# Fonte_Sim_trica_12V.net
KiCad netlist of a schematic drawn in EAGLE
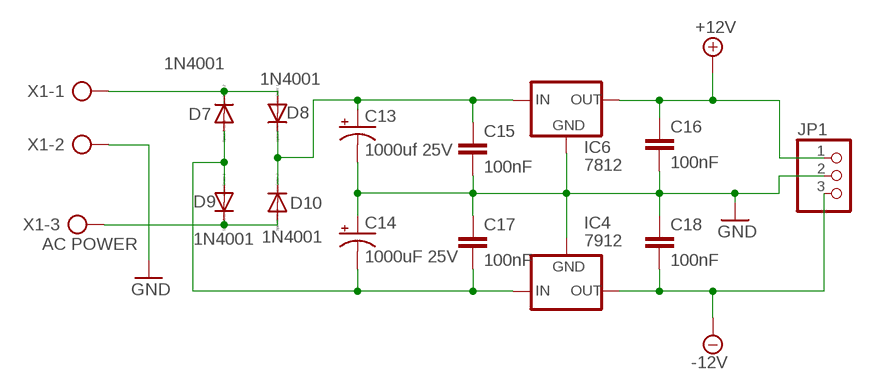
[diagram p0: schematic, sheet 1]

(export (version "E")
  (design (tool "Eeschema 10.0.6"))
  (components
    (comp (ref "C13")
      (value "1000uf 25V")
      (footprint "eagle-import:E5-10,5")
      (libsource (lib "eagle-import") (part "CPOL-USE5-10.5"))
    )
    (comp (ref "C14")
      (value "1000uF 25V")
      (footprint "eagle-import:E5-10,5")
      (libsource (lib "eagle-import") (part "CPOL-USE5-10.5"))
    )
    (comp (ref "C15")
      (value "100nF")
      (footprint "eagle-import:C025-040X050")
      (libsource (lib "eagle-import") (part "C-EU025-040X050"))
    )
    (comp (ref "C16")
      (value "100nF")
      (footprint "eagle-import:C025-040X050")
      (libsource (lib "eagle-import") (part "C-EU025-040X050"))
    )
    (comp (ref "C17")
      (value "100nF")
      (footprint "eagle-import:C025-040X050")
      (libsource (lib "eagle-import") (part "C-EU025-040X050"))
    )
    (comp (ref "C18")
      (value "100nF")
      (footprint "eagle-import:C025-040X050")
      (libsource (lib "eagle-import") (part "C-EU025-040X050"))
    )
    (comp (ref "D7")
      (value "1N4001")
      (footprint "eagle-import:DO41-10")
      (libsource (lib "eagle-import") (part "1N4004"))
    )
    (comp (ref "D8")
      (value "1N4001")
      (footprint "eagle-import:DO41-10")
      (libsource (lib "eagle-import") (part "1N4004"))
    )
    (comp (ref "D9")
      (value "1N4001")
      (footprint "eagle-import:DO41-10")
      (libsource (lib "eagle-import") (part "1N4004"))
    )
    (comp (ref "D10")
      (value "1N4001")
      (footprint "eagle-import:DO41-10")
      (libsource (lib "eagle-import") (part "1N4004"))
    )
    (comp (ref "IC4")
      (value "7912")
      (footprint "eagle-import:79XXS")
      (libsource (lib "eagle-import") (part "79XXS"))
    )
    (comp (ref "IC6")
      (value "7812")
      (footprint "eagle-import:78XXS")
      (libsource (lib "eagle-import") (part "78XXS"))
    )
    (comp (ref "JP1")
      (value "PINHD-1X3")
      (footprint "eagle-import:1X03")
      (libsource (lib "eagle-import") (part "PINHD-1X3"))
    )
    (comp (ref "X1")
      (value "AC POWER")
      (footprint "eagle-import:AK500_3")
      (libsource (lib "eagle-import") (part "AK500/3"))
    )
  )
  (nets
    (net (code "1") (name "+12V") (class "Default")
      (node (ref "C16") (pin "1") (pinfunction "1_1") (pintype "passive"))
      (node (ref "IC6") (pin "OUT") (pinfunction "OUT_OUT") (pintype "passive"))
      (node (ref "JP1") (pin "1") (pinfunction "1_1") (pintype "passive"))
    )
    (net (code "2") (name "-12V") (class "Default")
      (node (ref "C18") (pin "2") (pinfunction "2_2") (pintype "passive"))
      (node (ref "IC4") (pin "OUT") (pinfunction "OUT_OUT") (pintype "passive"))
      (node (ref "JP1") (pin "3") (pinfunction "3_3") (pintype "passive"))
    )
    (net (code "3") (name "GND") (class "Default")
      (node (ref "C13") (pin "-") (pinfunction "-_-") (pintype "passive"))
      (node (ref "C14") (pin "+") (pinfunction "+_+") (pintype "passive"))
      (node (ref "C15") (pin "2") (pinfunction "2_2") (pintype "passive"))
      (node (ref "C16") (pin "2") (pinfunction "2_2") (pintype "passive"))
      (node (ref "C17") (pin "1") (pinfunction "1_1") (pintype "passive"))
      (node (ref "C18") (pin "1") (pinfunction "1_1") (pintype "passive"))
      (node (ref "IC4") (pin "GND") (pinfunction "GND_GND") (pintype "input"))
      (node (ref "IC6") (pin "GND") (pinfunction "GND_GND") (pintype "input"))
      (node (ref "JP1") (pin "2") (pinfunction "2_2") (pintype "passive"))
      (node (ref "X1") (pin "2") (pinfunction "KL_2") (pintype "passive"))
    )
    (net (code "4") (name "Net-(C13-Pad+)") (class "Default")
      (node (ref "C13") (pin "+") (pinfunction "+_+") (pintype "passive"))
      (node (ref "C15") (pin "1") (pinfunction "1_1") (pintype "passive"))
      (node (ref "D10") (pin "C") (pinfunction "C_C") (pintype "passive"))
      (node (ref "D8") (pin "C") (pinfunction "C_C") (pintype "passive"))
      (node (ref "IC6") (pin "IN") (pinfunction "IN_IN") (pintype "input"))
    )
    (net (code "5") (name "Net-(C14-Pad-)") (class "Default")
      (node (ref "C14") (pin "-") (pinfunction "-_-") (pintype "passive"))
      (node (ref "C17") (pin "2") (pinfunction "2_2") (pintype "passive"))
      (node (ref "D7") (pin "A") (pinfunction "A_A") (pintype "passive"))
      (node (ref "D9") (pin "A") (pinfunction "A_A") (pintype "passive"))
      (node (ref "IC4") (pin "IN") (pinfunction "IN_IN") (pintype "input"))
    )
    (net (code "6") (name "Net-(X1A-KL)") (class "Default")
      (node (ref "D7") (pin "C") (pinfunction "C_C") (pintype "passive"))
      (node (ref "D8") (pin "A") (pinfunction "A_A") (pintype "passive"))
      (node (ref "X1") (pin "1") (pinfunction "KL_1") (pintype "passive"))
    )
    (net (code "7") (name "Net-(X1C-KL)") (class "Default")
      (node (ref "D10") (pin "A") (pinfunction "A_A") (pintype "passive"))
      (node (ref "D9") (pin "C") (pinfunction "C_C") (pintype "passive"))
      (node (ref "X1") (pin "3") (pinfunction "KL_3") (pintype "passive"))
    )
  )
)
